# Sensor_Acquisition_Board_Front_rev1.net
KiCad netlist of a schematic drawn in EAGLE
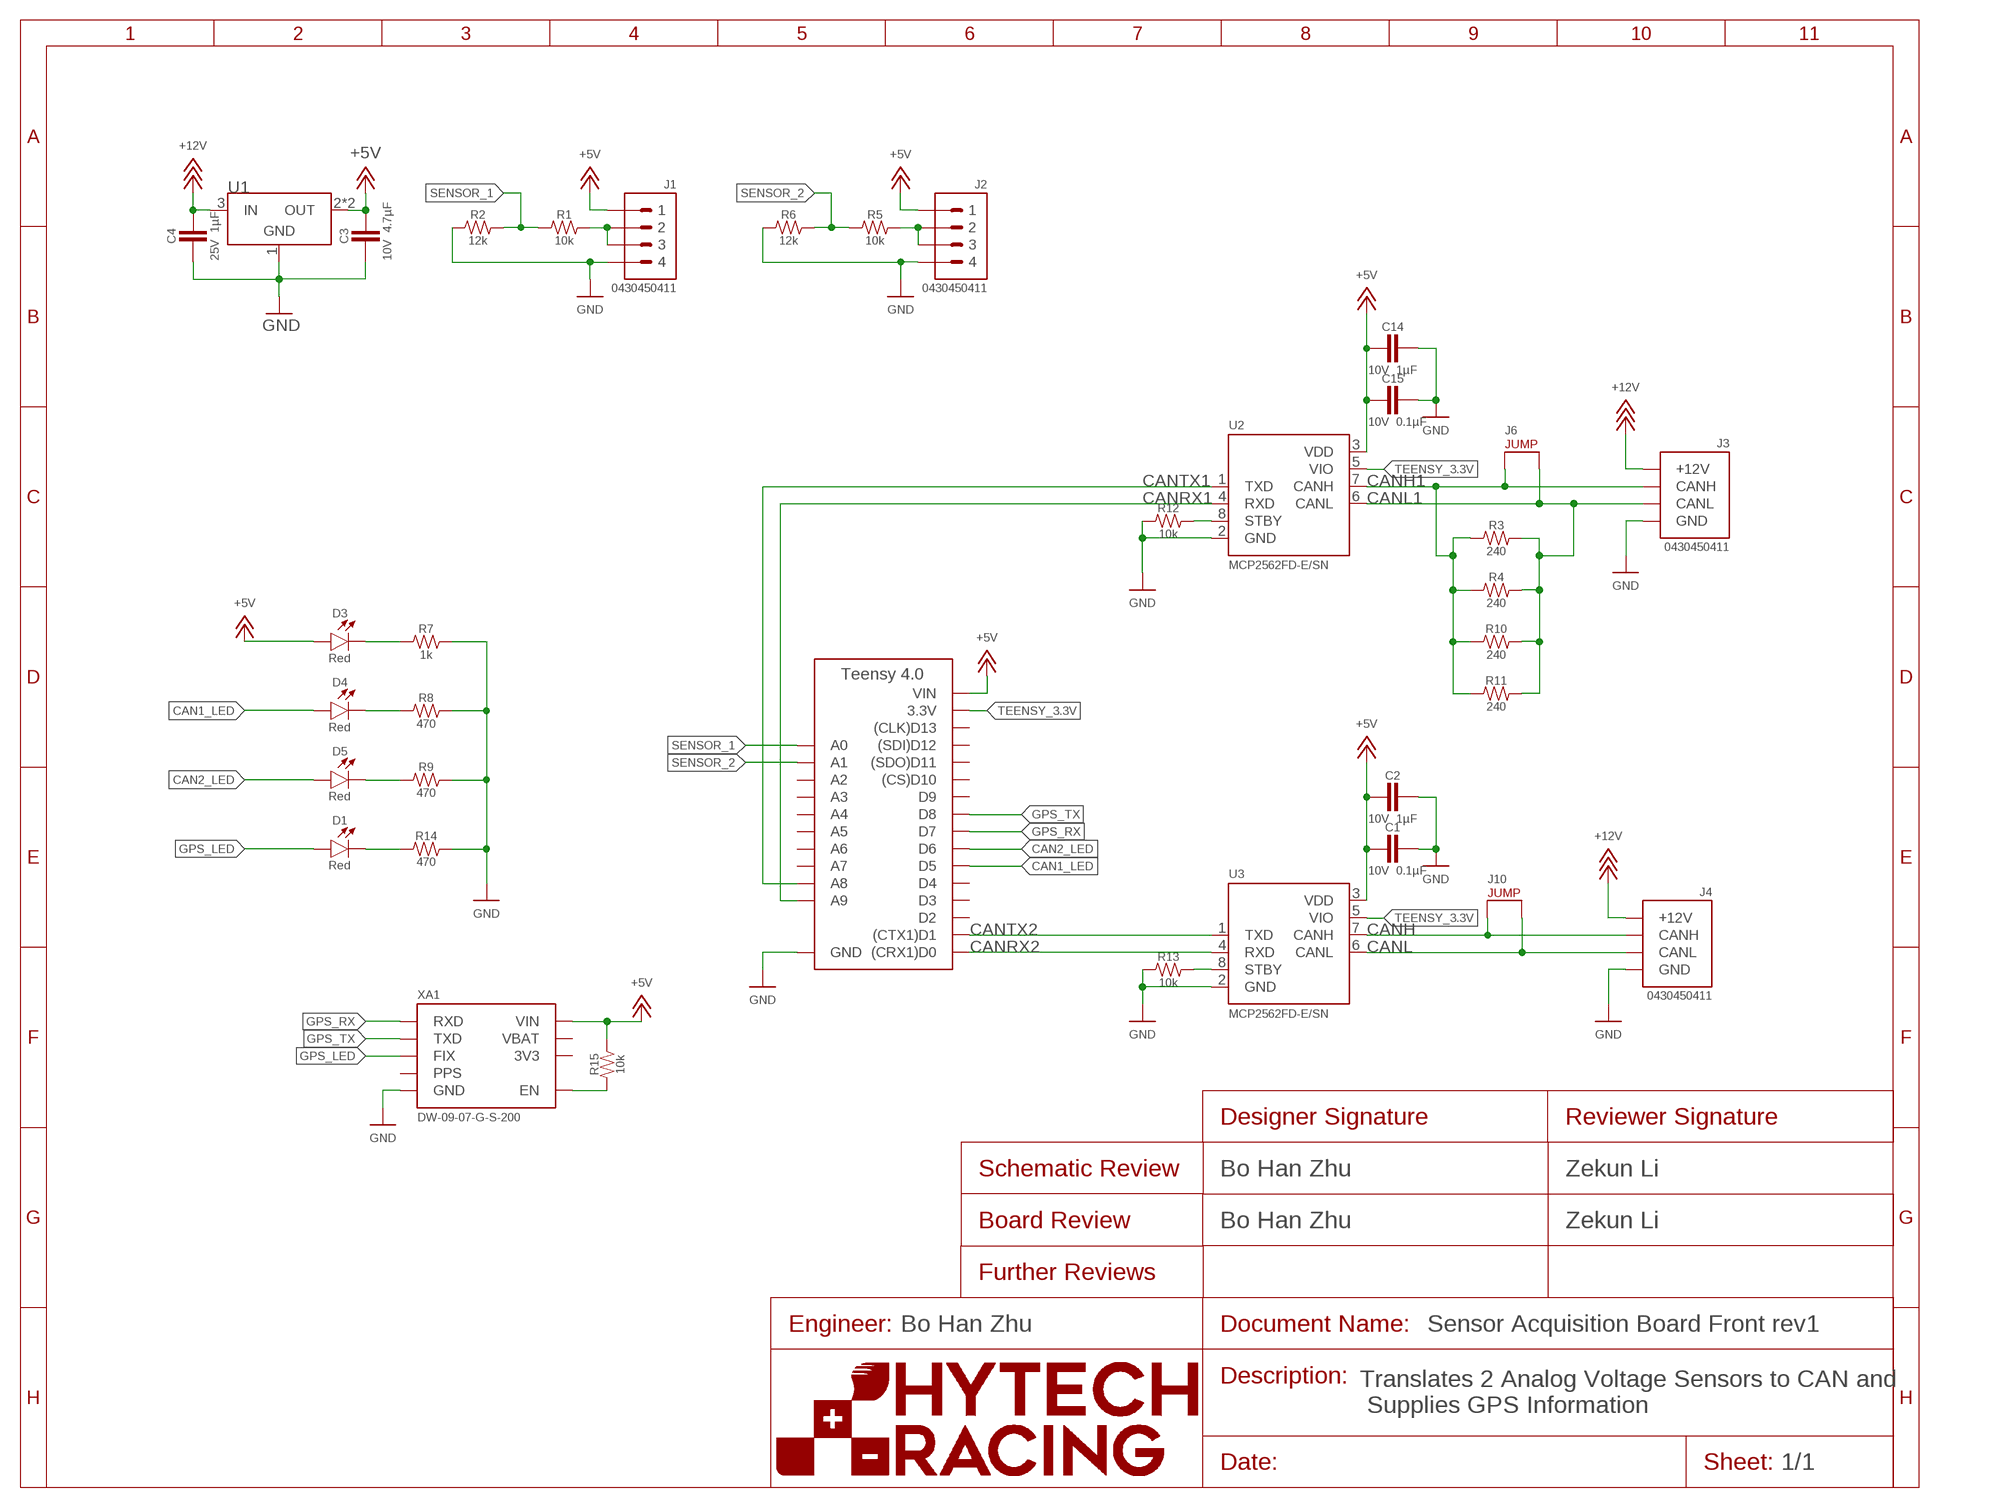
[diagram p0: schematic, sheet 1]

(export (version "E")
  (design (tool "Eeschema 10.0.6"))
  (components
    (comp (ref "A2")
      (value "TEENSY_4.0")
      (footprint "eagle-import:TEENSY_SHORT")
      (libsource (lib "eagle-import") (part "TEENSY_4.0"))
    )
    (comp (ref "C1")
      (value "CAPACITOR_0603_10V_0.1UF")
      (footprint "eagle-import:0603-CAP")
      (fields
        (field (name "CAPACITANCE") "0.1µF")
        (field (name "MANUFACTURER") "Vishay Vitramon")
        (field (name "MPN") "VJ0603Y104JXQPW1BC")
        (field (name "TOLERANCE") "5%")
        (field (name "VOLTAGE") "10V")
      )
      (libsource (lib "eagle-import") (part "CAPACITOR_?_060310V_0.1UF"))
    )
    (comp (ref "C2")
      (value "CAPACITOR_0603_10V_1UF")
      (footprint "eagle-import:0603-CAP")
      (fields
        (field (name "CAPACITANCE") "1µF")
        (field (name "MANUFACTURER") "Yageo")
        (field (name "MPN") "CC0603KRX7R6BB105")
        (field (name "TOLERANCE") "10%")
        (field (name "VOLTAGE") "10V")
      )
      (libsource (lib "eagle-import") (part "CAPACITOR_?_060310V_1UF"))
    )
    (comp (ref "C3")
      (value "CAPACITOR_0603_10V_4.7UF")
      (footprint "eagle-import:0603-CAP")
      (fields
        (field (name "CAPACITANCE") "4.7µF")
        (field (name "MANUFACTURER") "Samsung Electro-Mechanics")
        (field (name "MPN") "CL10A475KP8NNNC")
        (field (name "TOLERANCE") "10%")
        (field (name "VOLTAGE") "10V")
      )
      (libsource (lib "eagle-import") (part "CAPACITOR_?_060310V_4.7UF"))
    )
    (comp (ref "C4")
      (value "CAPACITOR_0603_25V_1UF")
      (footprint "eagle-import:0603-CAP")
      (fields
        (field (name "CAPACITANCE") "1µF")
        (field (name "MANUFACTURER") "Samsung Electro-Mechanics")
        (field (name "MPN") "CL10B105KA8NNNC")
        (field (name "TOLERANCE") "10%")
        (field (name "VOLTAGE") "25V")
      )
      (libsource (lib "eagle-import") (part "CAPACITOR_?_060325V_1UF"))
    )
    (comp (ref "C14")
      (value "CAPACITOR_0603_10V_1UF")
      (footprint "eagle-import:0603-CAP")
      (fields
        (field (name "CAPACITANCE") "1µF")
        (field (name "MANUFACTURER") "Yageo")
        (field (name "MPN") "CC0603KRX7R6BB105")
        (field (name "TOLERANCE") "10%")
        (field (name "VOLTAGE") "10V")
      )
      (libsource (lib "eagle-import") (part "CAPACITOR_?_060310V_1UF"))
    )
    (comp (ref "C15")
      (value "CAPACITOR_0603_10V_0.1UF")
      (footprint "eagle-import:0603-CAP")
      (fields
        (field (name "CAPACITANCE") "0.1µF")
        (field (name "MANUFACTURER") "Vishay Vitramon")
        (field (name "MPN") "VJ0603Y104JXQPW1BC")
        (field (name "TOLERANCE") "5%")
        (field (name "VOLTAGE") "10V")
      )
      (libsource (lib "eagle-import") (part "CAPACITOR_?_060310V_0.1UF"))
    )
    (comp (ref "D1")
      (value "LED_0603_RED")
      (footprint "eagle-import:0603-LED")
      (fields
        (field (name "COLOR") "Red")
        (field (name "MANUFACTURER") "Kingbright")
        (field (name "MPN") "APT1608SECK/J3-PRV")
      )
      (libsource (lib "eagle-import") (part "LED_?_0603RED"))
    )
    (comp (ref "D3")
      (value "LED_0603_RED")
      (footprint "eagle-import:0603-LED")
      (fields
        (field (name "COLOR") "Red")
        (field (name "MANUFACTURER") "Kingbright")
        (field (name "MPN") "APT1608SECK/J3-PRV")
      )
      (libsource (lib "eagle-import") (part "LED_?_0603RED"))
    )
    (comp (ref "D4")
      (value "LED_0603_RED")
      (footprint "eagle-import:0603-LED")
      (fields
        (field (name "COLOR") "Red")
        (field (name "MANUFACTURER") "Kingbright")
        (field (name "MPN") "APT1608SECK/J3-PRV")
      )
      (libsource (lib "eagle-import") (part "LED_?_0603RED"))
    )
    (comp (ref "D5")
      (value "LED_0603_RED")
      (footprint "eagle-import:0603-LED")
      (fields
        (field (name "COLOR") "Red")
        (field (name "MANUFACTURER") "Kingbright")
        (field (name "MPN") "APT1608SECK/J3-PRV")
      )
      (libsource (lib "eagle-import") (part "LED_?_0603RED"))
    )
    (comp (ref "J1")
      (value "CONNECTOR-4_μF_S_RA_")
      (footprint "eagle-import:MOLEX_MICROFIT_SMD_RIGHTANGLE_04_DUAL")
      (fields (field (name "MPN") "0430450411") (field (name "MANUFACTURER") "Molex"))
      (libsource (lib "eagle-import") (part "CONNECTOR-4_?_μF_S_RA"))
    )
    (comp (ref "J2")
      (value "CONNECTOR-4_μF_S_RA_")
      (footprint "eagle-import:MOLEX_MICROFIT_SMD_RIGHTANGLE_04_DUAL")
      (fields (field (name "MPN") "0430450411") (field (name "MANUFACTURER") "Molex"))
      (libsource (lib "eagle-import") (part "CONNECTOR-4_?_μF_S_RA"))
    )
    (comp (ref "J3")
      (value "CONNECTOR-CAN_μF_S_RA_")
      (footprint "eagle-import:MOLEX_MICROFIT_SMD_RIGHTANGLE_04_DUAL")
      (fields (field (name "MPN") "0430450411") (field (name "MANUFACTURER") "Molex"))
      (libsource (lib "eagle-import") (part "CONNECTOR-CAN_?_μF_S_RA"))
    )
    (comp (ref "J4")
      (value "CONNECTOR-CAN_μF_S_RA_")
      (footprint "eagle-import:MOLEX_MICROFIT_SMD_RIGHTANGLE_04_DUAL")
      (fields (field (name "MPN") "0430450411") (field (name "MANUFACTURER") "Molex"))
      (libsource (lib "eagle-import") (part "CONNECTOR-CAN_?_μF_S_RA"))
    )
    (comp (ref "J6")
      (value "JUMPER_0603_")
      (footprint "eagle-import:0603-RES")
      (fields (field (name "MPN") "RC0603FR-130RL") (field (name "MANUFACTURER") "YAGEO"))
      (libsource (lib "eagle-import") (part "JUMPER_?_0603"))
    )
    (comp (ref "J10")
      (value "JUMPER_0603_")
      (footprint "eagle-import:0603-RES")
      (fields (field (name "MPN") "RC0603FR-130RL") (field (name "MANUFACTURER") "YAGEO"))
      (libsource (lib "eagle-import") (part "JUMPER_?_0603"))
    )
    (comp (ref "R1")
      (value "RESISTOR_0603_10K")
      (footprint "eagle-import:0603-RES")
      (fields
        (field (name "MANUFACTURER") "Yageo")
        (field (name "MPN") "RC0603FR-0710KL")
        (field (name "POWER") "0.1W")
        (field (name "RESISTANCE") "10k")
      )
      (libsource (lib "eagle-import") (part "RESISTOR_?_060310K"))
    )
    (comp (ref "R2")
      (value "RESISTOR_0603_12K")
      (footprint "eagle-import:0603-RES")
      (fields
        (field (name "MANUFACTURER") "Yageo")
        (field (name "MPN") "RC0603FR-0712KL")
        (field (name "POWER") "0.1W")
        (field (name "RESISTANCE") "12k")
      )
      (libsource (lib "eagle-import") (part "RESISTOR_?_060312K"))
    )
    (comp (ref "R3")
      (value "RESISTOR_0603_240")
      (footprint "eagle-import:0603-RES")
      (fields
        (field (name "MANUFACTURER") "Yageo")
        (field (name "MPN") "RC0603FR-07240RL")
        (field (name "POWER") "0.1W")
        (field (name "RESISTANCE") "240")
      )
      (libsource (lib "eagle-import") (part "RESISTOR_?_0603240"))
    )
    (comp (ref "R4")
      (value "RESISTOR_0603_240")
      (footprint "eagle-import:0603-RES")
      (fields
        (field (name "MANUFACTURER") "Yageo")
        (field (name "MPN") "RC0603FR-07240RL")
        (field (name "POWER") "0.1W")
        (field (name "RESISTANCE") "240")
      )
      (libsource (lib "eagle-import") (part "RESISTOR_?_0603240"))
    )
    (comp (ref "R5")
      (value "RESISTOR_0603_10K")
      (footprint "eagle-import:0603-RES")
      (fields
        (field (name "MANUFACTURER") "Yageo")
        (field (name "MPN") "RC0603FR-0710KL")
        (field (name "POWER") "0.1W")
        (field (name "RESISTANCE") "10k")
      )
      (libsource (lib "eagle-import") (part "RESISTOR_?_060310K"))
    )
    (comp (ref "R6")
      (value "RESISTOR_0603_12K")
      (footprint "eagle-import:0603-RES")
      (fields
        (field (name "MANUFACTURER") "Yageo")
        (field (name "MPN") "RC0603FR-0712KL")
        (field (name "POWER") "0.1W")
        (field (name "RESISTANCE") "12k")
      )
      (libsource (lib "eagle-import") (part "RESISTOR_?_060312K"))
    )
    (comp (ref "R7")
      (value "RESISTOR_0603_1K")
      (footprint "eagle-import:0603-RES")
      (fields
        (field (name "MANUFACTURER") "Yageo")
        (field (name "MPN") "RC0603FR-071KL")
        (field (name "POWER") "0.1W")
        (field (name "RESISTANCE") "1k")
      )
      (libsource (lib "eagle-import") (part "RESISTOR_?_06031K"))
    )
    (comp (ref "R8")
      (value "RESISTOR_0603_470")
      (footprint "eagle-import:0603-RES")
      (fields
        (field (name "MANUFACTURER") "Panasonic Electronic Components")
        (field (name "MPN") "ERJ-PA3F4700V")
        (field (name "POWER") "0.25W")
        (field (name "RESISTANCE") "470")
      )
      (libsource (lib "eagle-import") (part "RESISTOR_?_0603470"))
    )
    (comp (ref "R9")
      (value "RESISTOR_0603_470")
      (footprint "eagle-import:0603-RES")
      (fields
        (field (name "MANUFACTURER") "Panasonic Electronic Components")
        (field (name "MPN") "ERJ-PA3F4700V")
        (field (name "POWER") "0.25W")
        (field (name "RESISTANCE") "470")
      )
      (libsource (lib "eagle-import") (part "RESISTOR_?_0603470"))
    )
    (comp (ref "R10")
      (value "RESISTOR_0603_240")
      (footprint "eagle-import:0603-RES")
      (fields
        (field (name "MANUFACTURER") "Yageo")
        (field (name "MPN") "RC0603FR-07240RL")
        (field (name "POWER") "0.1W")
        (field (name "RESISTANCE") "240")
      )
      (libsource (lib "eagle-import") (part "RESISTOR_?_0603240"))
    )
    (comp (ref "R11")
      (value "RESISTOR_0603_240")
      (footprint "eagle-import:0603-RES")
      (fields
        (field (name "MANUFACTURER") "Yageo")
        (field (name "MPN") "RC0603FR-07240RL")
        (field (name "POWER") "0.1W")
        (field (name "RESISTANCE") "240")
      )
      (libsource (lib "eagle-import") (part "RESISTOR_?_0603240"))
    )
    (comp (ref "R12")
      (value "RESISTOR_0603_10K")
      (footprint "eagle-import:0603-RES")
      (fields
        (field (name "MANUFACTURER") "Yageo")
        (field (name "MPN") "RC0603FR-0710KL")
        (field (name "POWER") "0.1W")
        (field (name "RESISTANCE") "10k")
      )
      (libsource (lib "eagle-import") (part "RESISTOR_?_060310K"))
    )
    (comp (ref "R13")
      (value "RESISTOR_0603_10K")
      (footprint "eagle-import:0603-RES")
      (fields
        (field (name "MANUFACTURER") "Yageo")
        (field (name "MPN") "RC0603FR-0710KL")
        (field (name "POWER") "0.1W")
        (field (name "RESISTANCE") "10k")
      )
      (libsource (lib "eagle-import") (part "RESISTOR_?_060310K"))
    )
    (comp (ref "R14")
      (value "RESISTOR_0603_470")
      (footprint "eagle-import:0603-RES")
      (fields
        (field (name "MANUFACTURER") "Panasonic Electronic Components")
        (field (name "MPN") "ERJ-PA3F4700V")
        (field (name "POWER") "0.25W")
        (field (name "RESISTANCE") "470")
      )
      (libsource (lib "eagle-import") (part "RESISTOR_?_0603470"))
    )
    (comp (ref "R15")
      (value "RESISTOR_0603_10K")
      (footprint "eagle-import:0603-RES")
      (fields
        (field (name "MANUFACTURER") "Yageo")
        (field (name "MPN") "RC0603FR-0710KL")
        (field (name "POWER") "0.1W")
        (field (name "RESISTANCE") "10k")
      )
      (libsource (lib "eagle-import") (part "RESISTOR_?_060310K"))
    )
    (comp (ref "U1")
      (value "VOLTAGE_REGULATOR_SOT-223_5V")
      (footprint "eagle-import:SOT-223")
      (fields (field (name "MANUFACTURER") "STMicroelectronics") (field (name "MPN") "LDL1117S50R"))
      (libsource (lib "eagle-import") (part "VOLTAGE_REGULATOR_?_SOT-2235V"))
    )
    (comp (ref "U2")
      (value "MCP2562FD")
      (footprint "eagle-import:SOIC-08(NARROW,0.15_)")
      (fields (field (name "MPN") "MCP2562FD-E/SN") (field (name "MANUFACTURER") "Microchip Technology"))
      (libsource (lib "eagle-import") (part "MCP2562FD"))
    )
    (comp (ref "U3")
      (value "MCP2562FD")
      (footprint "eagle-import:SOIC-08(NARROW,0.15_)")
      (fields (field (name "MPN") "MCP2562FD-E/SN") (field (name "MANUFACTURER") "Microchip Technology"))
      (libsource (lib "eagle-import") (part "MCP2562FD"))
    )
    (comp (ref "XA1")
      (value "ULTIMATE_GPS")
      (footprint "eagle-import:ULTIMATE_GPS")
      (fields (field (name "MPN") "DW-09-07-G-S-200") (field (name "MANUFACTURER") "Samtec Inc."))
      (libsource (lib "eagle-import") (part "ULTIMATE_GPS"))
    )
  )
  (nets
    (net (code "1") (name "+5V") (class "Default")
      (node (ref "A2") (pin "VIN") (pinfunction "VIN_VIN") (pintype "power_in"))
      (node (ref "C1") (pin "2") (pinfunction "2_2") (pintype "passive"))
      (node (ref "C14") (pin "2") (pinfunction "2_2") (pintype "passive"))
      (node (ref "C15") (pin "2") (pinfunction "2_2") (pintype "passive"))
      (node (ref "C2") (pin "2") (pinfunction "2_2") (pintype "passive"))
      (node (ref "C3") (pin "1") (pinfunction "1_1") (pintype "passive"))
      (node (ref "D3") (pin "2") (pinfunction "A_2") (pintype "passive"))
      (node (ref "J1") (pin "1") (pinfunction "1_1") (pintype "passive"))
      (node (ref "J2") (pin "1") (pinfunction "1_1") (pintype "passive"))
      (node (ref "R15") (pin "2") (pinfunction "2_2") (pintype "passive"))
      (node (ref "U1") (pin "2") (pinfunction "OUT_2") (pintype "power_in"))
      (node (ref "U1") (pin "4") (pinfunction "OUT_4") (pintype "power_in"))
      (node (ref "U2") (pin "3") (pinfunction "VDD_3") (pintype "power_in"))
      (node (ref "U3") (pin "3") (pinfunction "VDD_3") (pintype "power_in"))
      (node (ref "XA1") (pin "VIN") (pinfunction "VIN_VIN") (pintype "power_in"))
    )
    (net (code "2") (name "+12V") (class "Default")
      (node (ref "C4") (pin "1") (pinfunction "1_1") (pintype "passive"))
      (node (ref "J3") (pin "1") (pinfunction "+12V_1") (pintype "power_in"))
      (node (ref "J4") (pin "1") (pinfunction "+12V_1") (pintype "power_in"))
      (node (ref "U1") (pin "3") (pinfunction "IN_3") (pintype "power_in"))
    )
    (net (code "3") (name "/3V3") (class "Default")
      (node (ref "XA1") (pin "3.3V") (pinfunction "3V3_3.3V") (pintype "power_in"))
    )
    (net (code "4") (name "/CANH") (class "Default")
      (node (ref "J10") (pin "1") (pinfunction "1_1") (pintype "passive"))
      (node (ref "J4") (pin "4") (pinfunction "CANH_4") (pintype "bidirectional"))
      (node (ref "U3") (pin "7") (pinfunction "CANH_7") (pintype "bidirectional"))
    )
    (net (code "5") (name "/CANH1") (class "Default")
      (node (ref "J3") (pin "4") (pinfunction "CANH_4") (pintype "bidirectional"))
      (node (ref "J6") (pin "1") (pinfunction "1_1") (pintype "passive"))
      (node (ref "R10") (pin "1") (pinfunction "1_1") (pintype "passive"))
      (node (ref "R11") (pin "1") (pinfunction "1_1") (pintype "passive"))
      (node (ref "R3") (pin "1") (pinfunction "1_1") (pintype "passive"))
      (node (ref "R4") (pin "1") (pinfunction "1_1") (pintype "passive"))
      (node (ref "U2") (pin "7") (pinfunction "CANH_7") (pintype "bidirectional"))
    )
    (net (code "6") (name "/CANL") (class "Default")
      (node (ref "J10") (pin "2") (pinfunction "2_2") (pintype "passive"))
      (node (ref "J4") (pin "3") (pinfunction "CANL_3") (pintype "bidirectional"))
      (node (ref "U3") (pin "6") (pinfunction "CANL_6") (pintype "bidirectional"))
    )
    (net (code "7") (name "/CANL1") (class "Default")
      (node (ref "J3") (pin "3") (pinfunction "CANL_3") (pintype "bidirectional"))
      (node (ref "J6") (pin "2") (pinfunction "2_2") (pintype "passive"))
      (node (ref "R10") (pin "2") (pinfunction "2_2") (pintype "passive"))
      (node (ref "R11") (pin "2") (pinfunction "2_2") (pintype "passive"))
      (node (ref "R3") (pin "2") (pinfunction "2_2") (pintype "passive"))
      (node (ref "R4") (pin "2") (pinfunction "2_2") (pintype "passive"))
      (node (ref "U2") (pin "6") (pinfunction "CANL_6") (pintype "bidirectional"))
    )
    (net (code "8") (name "/CANRX1") (class "Default")
      (node (ref "A2") (pin "D23") (pinfunction "A9_D23") (pintype "bidirectional"))
      (node (ref "U2") (pin "4") (pinfunction "RXD_4") (pintype "output"))
    )
    (net (code "9") (name "/CANRX2") (class "Default")
      (node (ref "A2") (pin "D0") (pinfunction "(CRX1)D0_D0") (pintype "bidirectional"))
      (node (ref "U3") (pin "4") (pinfunction "RXD_4") (pintype "output"))
    )
    (net (code "10") (name "/CANTX1") (class "Default")
      (node (ref "A2") (pin "D22") (pinfunction "A8_D22") (pintype "bidirectional"))
      (node (ref "U2") (pin "1") (pinfunction "TXD_1") (pintype "input"))
    )
    (net (code "11") (name "/CANTX2") (class "Default")
      (node (ref "A2") (pin "D1") (pinfunction "(CTX1)D1_D1") (pintype "bidirectional"))
      (node (ref "U3") (pin "1") (pinfunction "TXD_1") (pintype "input"))
    )
    (net (code "12") (name "/VBAT") (class "Default")
      (node (ref "XA1") (pin "VBAT") (pinfunction "VBAT_VBAT") (pintype "power_in"))
    )
    (net (code "13") (name "CAN1_LED") (class "Default")
      (node (ref "A2") (pin "D5") (pinfunction "D5_D5") (pintype "bidirectional"))
      (node (ref "D4") (pin "2") (pinfunction "A_2") (pintype "passive"))
    )
    (net (code "14") (name "CAN2_LED") (class "Default")
      (node (ref "A2") (pin "D6") (pinfunction "D6_D6") (pintype "bidirectional"))
      (node (ref "D5") (pin "2") (pinfunction "A_2") (pintype "passive"))
    )
    (net (code "15") (name "GND") (class "Default")
      (node (ref "A2") (pin "AGND/GND") (pinfunction "GND_AGND/GND") (pintype "power_in"))
      (node (ref "A2") (pin "GND") (pinfunction "GND_GND") (pintype "power_in"))
      (node (ref "C1") (pin "1") (pinfunction "1_1") (pintype "passive"))
      (node (ref "C14") (pin "1") (pinfunction "1_1") (pintype "passive"))
      (node (ref "C15") (pin "1") (pinfunction "1_1") (pintype "passive"))
      (node (ref "C2") (pin "1") (pinfunction "1_1") (pintype "passive"))
      (node (ref "C3") (pin "2") (pinfunction "2_2") (pintype "passive"))
      (node (ref "C4") (pin "2") (pinfunction "2_2") (pintype "passive"))
      (node (ref "J1") (pin "4") (pinfunction "4_4") (pintype "passive"))
      (node (ref "J2") (pin "4") (pinfunction "4_4") (pintype "passive"))
      (node (ref "J3") (pin "2") (pinfunction "GND_2") (pintype "power_in"))
      (node (ref "J4") (pin "2") (pinfunction "GND_2") (pintype "power_in"))
      (node (ref "R12") (pin "1") (pinfunction "1_1") (pintype "passive"))
      (node (ref "R13") (pin "1") (pinfunction "1_1") (pintype "passive"))
      (node (ref "R14") (pin "2") (pinfunction "2_2") (pintype "passive"))
      (node (ref "R2") (pin "1") (pinfunction "1_1") (pintype "passive"))
      (node (ref "R6") (pin "1") (pinfunction "1_1") (pintype "passive"))
      (node (ref "R7") (pin "2") (pinfunction "2_2") (pintype "passive"))
      (node (ref "R8") (pin "2") (pinfunction "2_2") (pintype "passive"))
      (node (ref "R9") (pin "2") (pinfunction "2_2") (pintype "passive"))
      (node (ref "U1") (pin "1") (pinfunction "GND_1") (pintype "power_in"))
      (node (ref "U2") (pin "2") (pinfunction "GND_2") (pintype "power_in"))
      (node (ref "U3") (pin "2") (pinfunction "GND_2") (pintype "power_in"))
      (node (ref "XA1") (pin "GND") (pinfunction "GND_GND") (pintype "power_in"))
    )
    (net (code "16") (name "GPS_LED") (class "Default")
      (node (ref "D1") (pin "2") (pinfunction "A_2") (pintype "passive"))
      (node (ref "XA1") (pin "FIX") (pinfunction "FIX_FIX") (pintype "output"))
    )
    (net (code "17") (name "GPS_RX") (class "Default")
      (node (ref "A2") (pin "D7") (pinfunction "D7_D7") (pintype "bidirectional"))
      (node (ref "XA1") (pin "RX") (pinfunction "RXD_RX") (pintype "input"))
    )
    (net (code "18") (name "GPS_TX") (class "Default")
      (node (ref "A2") (pin "D8") (pinfunction "D8_D8") (pintype "bidirectional"))
      (node (ref "XA1") (pin "TX") (pinfunction "TXD_TX") (pintype "output"))
    )
    (net (code "19") (name "Net-(D1-C)") (class "Default")
      (node (ref "D1") (pin "1") (pinfunction "C_1") (pintype "passive"))
      (node (ref "R14") (pin "1") (pinfunction "1_1") (pintype "passive"))
    )
    (net (code "20") (name "Net-(D3-C)") (class "Default")
      (node (ref "D3") (pin "1") (pinfunction "C_1") (pintype "passive"))
      (node (ref "R7") (pin "1") (pinfunction "1_1") (pintype "passive"))
    )
    (net (code "21") (name "Net-(D4-C)") (class "Default")
      (node (ref "D4") (pin "1") (pinfunction "C_1") (pintype "passive"))
      (node (ref "R8") (pin "1") (pinfunction "1_1") (pintype "passive"))
    )
    (net (code "22") (name "Net-(D5-C)") (class "Default")
      (node (ref "D5") (pin "1") (pinfunction "C_1") (pintype "passive"))
      (node (ref "R9") (pin "1") (pinfunction "1_1") (pintype "passive"))
    )
    (net (code "23") (name "Net-(J1-Pad2)") (class "Default")
      (node (ref "J1") (pin "2") (pinfunction "2_2") (pintype "passive"))
      (node (ref "J1") (pin "3") (pinfunction "3_3") (pintype "passive"))
      (node (ref "R1") (pin "2") (pinfunction "2_2") (pintype "passive"))
    )
    (net (code "24") (name "Net-(J2-Pad2)") (class "Default")
      (node (ref "J2") (pin "2") (pinfunction "2_2") (pintype "passive"))
      (node (ref "J2") (pin "3") (pinfunction "3_3") (pintype "passive"))
      (node (ref "R5") (pin "2") (pinfunction "2_2") (pintype "passive"))
    )
    (net (code "25") (name "Net-(R15-Pad1)") (class "Default")
      (node (ref "R15") (pin "1") (pinfunction "1_1") (pintype "passive"))
      (node (ref "XA1") (pin "EN") (pinfunction "EN_EN") (pintype "input"))
    )
    (net (code "26") (name "Net-(U2-STBY)") (class "Default")
      (node (ref "R12") (pin "2") (pinfunction "2_2") (pintype "passive"))
      (node (ref "U2") (pin "8") (pinfunction "STBY_8") (pintype "passive"))
    )
    (net (code "27") (name "Net-(U3-STBY)") (class "Default")
      (node (ref "R13") (pin "2") (pinfunction "2_2") (pintype "passive"))
      (node (ref "U3") (pin "8") (pinfunction "STBY_8") (pintype "passive"))
    )
    (net (code "28") (name "SENSOR_1") (class "Default")
      (node (ref "A2") (pin "D14") (pinfunction "A0_D14") (pintype "bidirectional"))
      (node (ref "R1") (pin "1") (pinfunction "1_1") (pintype "passive"))
      (node (ref "R2") (pin "2") (pinfunction "2_2") (pintype "passive"))
    )
    (net (code "29") (name "SENSOR_2") (class "Default")
      (node (ref "A2") (pin "D15") (pinfunction "A1_D15") (pintype "bidirectional"))
      (node (ref "R5") (pin "1") (pinfunction "1_1") (pintype "passive"))
      (node (ref "R6") (pin "2") (pinfunction "2_2") (pintype "passive"))
    )
    (net (code "30") (name "TEENSY_3.3V") (class "Default")
      (node (ref "A2") (pin "3.3V") (pinfunction "3.3V_3.3V") (pintype "power_in"))
      (node (ref "U2") (pin "5") (pinfunction "VIO_5") (pintype "power_in"))
      (node (ref "U3") (pin "5") (pinfunction "VIO_5") (pintype "power_in"))
    )
    (net (code "31") (name "unconnected-(A2-(CLK)D13-PadD13)") (class "Default")
      (node (ref "A2") (pin "D13") (pinfunction "(CLK)D13_D13") (pintype "bidirectional"))
    )
    (net (code "32") (name "unconnected-(A2-(CS)D10-PadD10)") (class "Default")
      (node (ref "A2") (pin "D10") (pinfunction "(CS)D10_D10") (pintype "bidirectional"))
    )
    (net (code "33") (name "unconnected-(A2-(SDI)D12-PadD12)") (class "Default")
      (node (ref "A2") (pin "D12") (pinfunction "(SDI)D12_D12") (pintype "bidirectional"))
    )
    (net (code "34") (name "unconnected-(A2-(SDO)D11-PadD11)") (class "Default")
      (node (ref "A2") (pin "D11") (pinfunction "(SDO)D11_D11") (pintype "bidirectional"))
    )
    (net (code "35") (name "unconnected-(A2-A2-PadD16)") (class "Default")
      (node (ref "A2") (pin "D16") (pinfunction "A2_D16") (pintype "bidirectional"))
    )
    (net (code "36") (name "unconnected-(A2-A3-PadD17)") (class "Default")
      (node (ref "A2") (pin "D17") (pinfunction "A3_D17") (pintype "bidirectional"))
    )
    (net (code "37") (name "unconnected-(A2-A4-PadD18)") (class "Default")
      (node (ref "A2") (pin "D18") (pinfunction "A4_D18") (pintype "bidirectional"))
    )
    (net (code "38") (name "unconnected-(A2-A5-PadD19)") (class "Default")
      (node (ref "A2") (pin "D19") (pinfunction "A5_D19") (pintype "bidirectional"))
    )
    (net (code "39") (name "unconnected-(A2-A6-PadD20)") (class "Default")
      (node (ref "A2") (pin "D20") (pinfunction "A6_D20") (pintype "bidirectional"))
    )
    (net (code "40") (name "unconnected-(A2-A7-PadD21)") (class "Default")
      (node (ref "A2") (pin "D21") (pinfunction "A7_D21") (pintype "bidirectional"))
    )
    (net (code "41") (name "unconnected-(A2-PadD2)") (class "Default")
      (node (ref "A2") (pin "D2") (pinfunction "D2_D2") (pintype "bidirectional"))
    )
    (net (code "42") (name "unconnected-(A2-PadD3)") (class "Default")
      (node (ref "A2") (pin "D3") (pinfunction "D3_D3") (pintype "bidirectional"))
    )
    (net (code "43") (name "unconnected-(A2-PadD4)") (class "Default")
      (node (ref "A2") (pin "D4") (pinfunction "D4_D4") (pintype "bidirectional"))
    )
    (net (code "44") (name "unconnected-(A2-PadD9)") (class "Default")
      (node (ref "A2") (pin "D9") (pinfunction "D9_D9") (pintype "bidirectional"))
    )
    (net (code "45") (name "unconnected-(XA1-PadPPS)") (class "Default")
      (node (ref "XA1") (pin "PPS") (pinfunction "PPS_PPS") (pintype "output"))
    )
  )
)
